# lucadogtag_sheet.net
KiCad netlist of a schematic drawn in Altium Designer
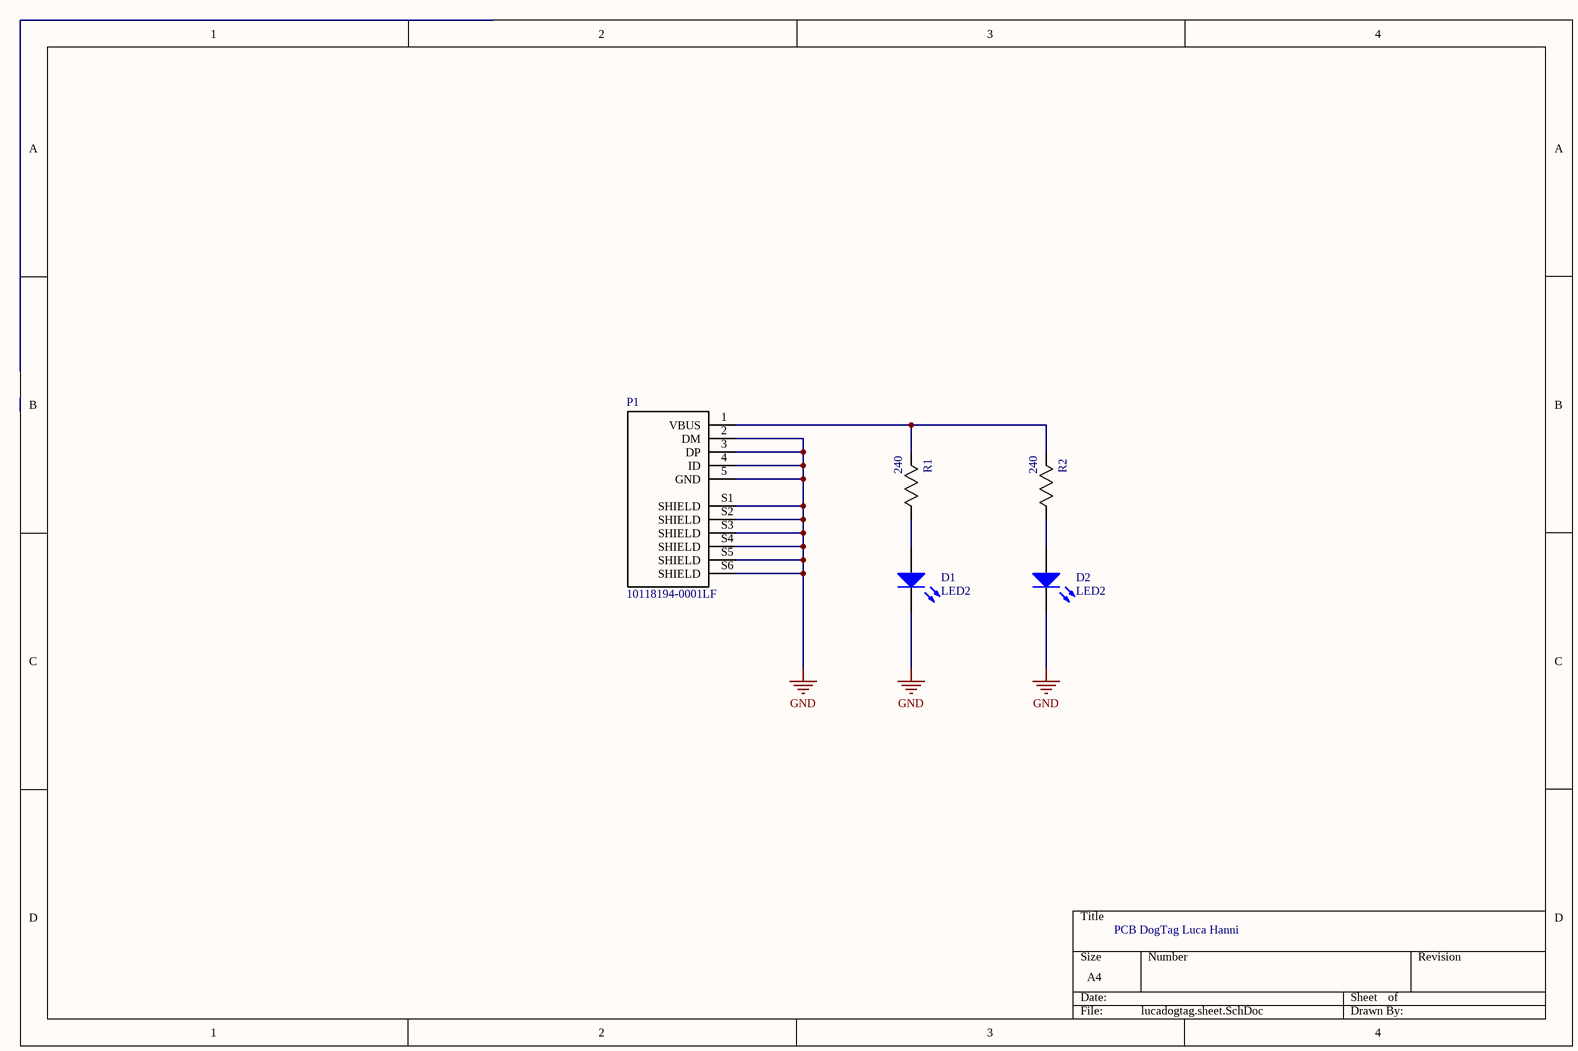
[diagram p0: lucadogtag.sheet.SchDoc]

(export (version "E")
  (design (tool "Eeschema 10.0.6"))
  (components
    (comp (ref "D1")
      (value "LED2")
      (footprint "3.2X1.6X1.1")
      (description "Typical RED, GREEN, YELLOW, AMBER GaAs LED")
      (fields (field (name "PUBLISHER") "Altium Limited"))
      (libsource (lib "Miscellaneous Devices") (part "LED2"))
    )
    (comp (ref "D2")
      (value "LED2")
      (footprint "3.2X1.6X1.1")
      (description "Typical RED, GREEN, YELLOW, AMBER GaAs LED")
      (fields (field (name "PUBLISHER") "Altium Limited"))
      (libsource (lib "Miscellaneous Devices") (part "LED2"))
    )
    (comp (ref "P1")
      (value "10118194-0001LF")
      (footprint "USB Micro B Receptacle")
      (description "USB - micro B USB 2.0 Receptacle Connector 5 Position Surface Mount, Right Angle; Through Hole")
      (fields (field (name "MF") "Amphenol ICC (FCI)"))
      (libsource (lib "AltiumLibraries") (part "USB Micro B Receptacle"))
    )
    (comp (ref "R1")
      (value "240")
      (footprint "0805")
      (description "RES SMD 240 OHM 5% 1/8W 0805")
      (fields (field (name "TOLERANCE") "5%"))
      (libsource (lib "AltiumLibraries") (part "RES 240.0 1/8W"))
    )
    (comp (ref "R2")
      (value "240")
      (footprint "0805")
      (description "RES SMD 240 OHM 5% 1/8W 0805")
      (fields (field (name "TOLERANCE") "5%"))
      (libsource (lib "AltiumLibraries") (part "RES 240.0 1/8W"))
    )
  )
  (nets
    (net (code "1") (name "GND") (class "Default")
      (node (ref "D1") (pin "2") (pinfunction "K_2") (pintype "passive"))
      (node (ref "D2") (pin "2") (pinfunction "K_2") (pintype "passive"))
      (node (ref "P1") (pin "2") (pinfunction "DM_2") (pintype "passive"))
      (node (ref "P1") (pin "3") (pinfunction "DP_3") (pintype "passive"))
      (node (ref "P1") (pin "4") (pinfunction "ID_4") (pintype "passive"))
      (node (ref "P1") (pin "5") (pinfunction "GND_5") (pintype "passive"))
      (node (ref "P1") (pin "S1") (pinfunction "SHIELD_S1") (pintype "passive"))
      (node (ref "P1") (pin "S2") (pinfunction "SHIELD_S2") (pintype "passive"))
      (node (ref "P1") (pin "S3") (pinfunction "SHIELD_S3") (pintype "passive"))
      (node (ref "P1") (pin "S4") (pinfunction "SHIELD_S4") (pintype "passive"))
      (node (ref "P1") (pin "S5") (pinfunction "SHIELD_S5") (pintype "passive"))
      (node (ref "P1") (pin "S6") (pinfunction "SHIELD_S6") (pintype "passive"))
    )
    (net (code "2") (name "Net-(D1-A)") (class "Default")
      (node (ref "D1") (pin "1") (pinfunction "A_1") (pintype "passive"))
      (node (ref "R1") (pin "1") (pinfunction "R1_1") (pintype "passive"))
    )
    (net (code "3") (name "Net-(D2-A)") (class "Default")
      (node (ref "D2") (pin "1") (pinfunction "A_1") (pintype "passive"))
      (node (ref "R2") (pin "1") (pinfunction "R1_1") (pintype "passive"))
    )
    (net (code "4") (name "Net-(P1-VBUS)") (class "Default")
      (node (ref "P1") (pin "1") (pinfunction "VBUS_1") (pintype "passive"))
      (node (ref "R1") (pin "2") (pinfunction "R2_2") (pintype "passive"))
      (node (ref "R2") (pin "2") (pinfunction "R2_2") (pintype "passive"))
    )
  )
)
